# Singularitron_Module_Template.net
KiCad netlist of a schematic drawn in EAGLE
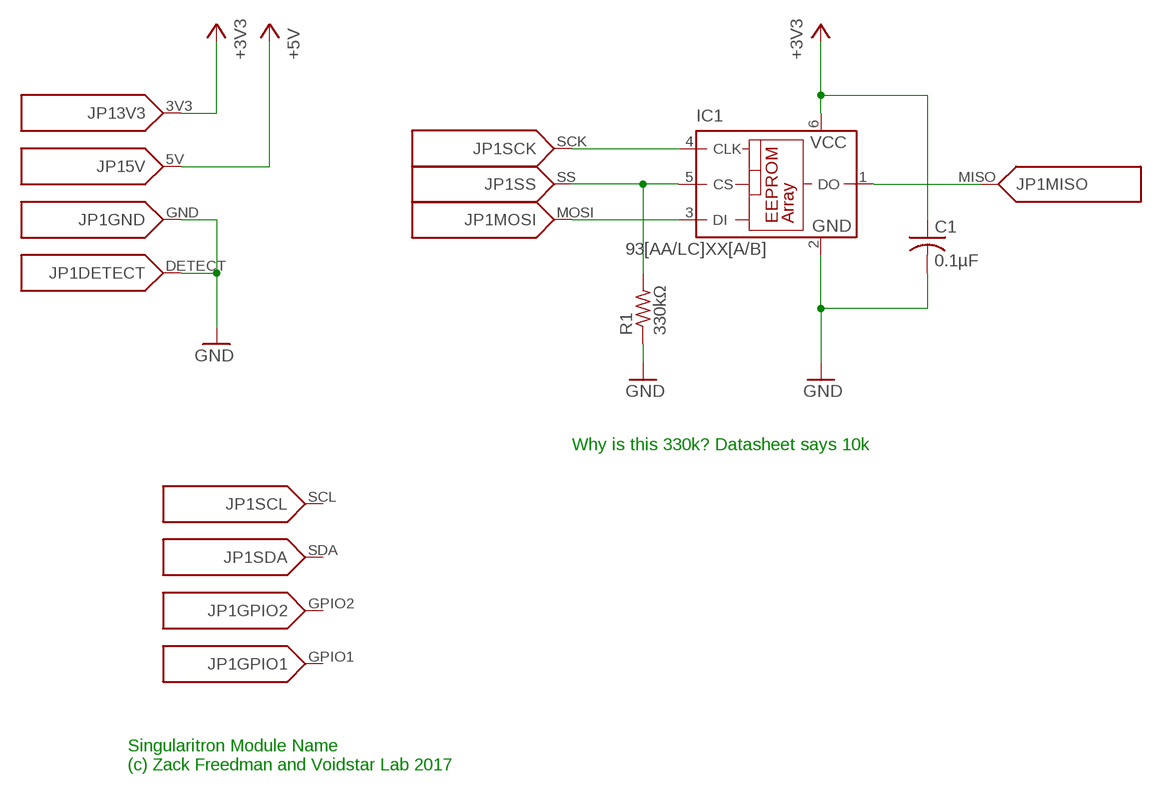
[diagram p0: schematic, sheet 1]

(export (version "E")
  (design (tool "Eeschema 10.0.6"))
  (components
    (comp (ref "C1")
      (value "0.1µF")
      (footprint "eagle-import:C0603")
      (libsource (lib "eagle-import") (part "C-USC0603"))
    )
    (comp (ref "IC1")
      (value "93[AA/LC]XX[A/B]")
      (footprint "eagle-import:SOT23-6")
      (fields (field (name "MPN") "93AA76AT-I/OT"))
      (libsource (lib "eagle-import") (part "9376?AAA"))
    )
    (comp (ref "JP1")
      (value "SINGULARITRON_CART_BASE")
      (footprint "eagle-import:SINGULARITRON_CART_BASE")
      (libsource (lib "eagle-import") (part "SINGULARITRON_CART_BASE"))
    )
    (comp (ref "R1")
      (value "330kΩ")
      (footprint "eagle-import:R0603")
      (libsource (lib "eagle-import") (part "R-US_R0603"))
    )
  )
  (nets
    (net (code "1") (name "+3V3") (class "Default")
      (node (ref "C1") (pin "1") (pinfunction "1_1") (pintype "passive"))
      (node (ref "IC1") (pin "6") (pinfunction "VCC_6") (pintype "power_in"))
      (node (ref "JP1") (pin "3V3") (pinfunction "P$1_3V3") (pintype "bidirectional"))
    )
    (net (code "2") (name "+5V") (class "Default")
      (node (ref "JP1") (pin "5V") (pinfunction "P$1_5V") (pintype "bidirectional"))
    )
    (net (code "3") (name "GND") (class "Default")
      (node (ref "C1") (pin "2") (pinfunction "2_2") (pintype "passive"))
      (node (ref "IC1") (pin "2") (pinfunction "GND_2") (pintype "power_in"))
      (node (ref "JP1") (pin "DETECT") (pinfunction "P$1_DETECT") (pintype "bidirectional"))
      (node (ref "JP1") (pin "GND") (pinfunction "P$1_GND") (pintype "bidirectional"))
      (node (ref "R1") (pin "1") (pinfunction "1_1") (pintype "passive"))
    )
    (net (code "4") (name "Net-(IC1-CLK)") (class "Default")
      (node (ref "IC1") (pin "4") (pinfunction "CLK_4") (pintype "input"))
      (node (ref "JP1") (pin "SCK") (pinfunction "P$1_SCK") (pintype "bidirectional"))
    )
    (net (code "5") (name "Net-(IC1-CS)") (class "Default")
      (node (ref "IC1") (pin "5") (pinfunction "CS_5") (pintype "input"))
      (node (ref "JP1") (pin "SS") (pinfunction "P$1_SS") (pintype "bidirectional"))
      (node (ref "R1") (pin "2") (pinfunction "2_2") (pintype "passive"))
    )
    (net (code "6") (name "Net-(IC1-DI)") (class "Default")
      (node (ref "IC1") (pin "3") (pinfunction "DI_3") (pintype "input"))
      (node (ref "JP1") (pin "MOSI") (pinfunction "P$1_MOSI") (pintype "bidirectional"))
    )
    (net (code "7") (name "Net-(IC1-DO)") (class "Default")
      (node (ref "IC1") (pin "1") (pinfunction "DO_1") (pintype "tri_state"))
      (node (ref "JP1") (pin "MISO") (pinfunction "P$1_MISO") (pintype "bidirectional"))
    )
    (net (code "8") (name "unconnected-(JP1E-P$1-PadGPIO1)") (class "Default")
      (node (ref "JP1") (pin "GPIO1") (pinfunction "P$1_GPIO1") (pintype "bidirectional"))
    )
    (net (code "9") (name "unconnected-(JP1F-P$1-PadGPIO2)") (class "Default")
      (node (ref "JP1") (pin "GPIO2") (pinfunction "P$1_GPIO2") (pintype "bidirectional"))
    )
    (net (code "10") (name "unconnected-(JP1J-P$1-PadSCL)") (class "Default")
      (node (ref "JP1") (pin "SCL") (pinfunction "P$1_SCL") (pintype "bidirectional"))
    )
    (net (code "11") (name "unconnected-(JP1K-P$1-PadSDA)") (class "Default")
      (node (ref "JP1") (pin "SDA") (pinfunction "P$1_SDA") (pintype "bidirectional"))
    )
  )
)
